# Digital_PWR.net
KiCad netlist of a schematic drawn in Altium Designer
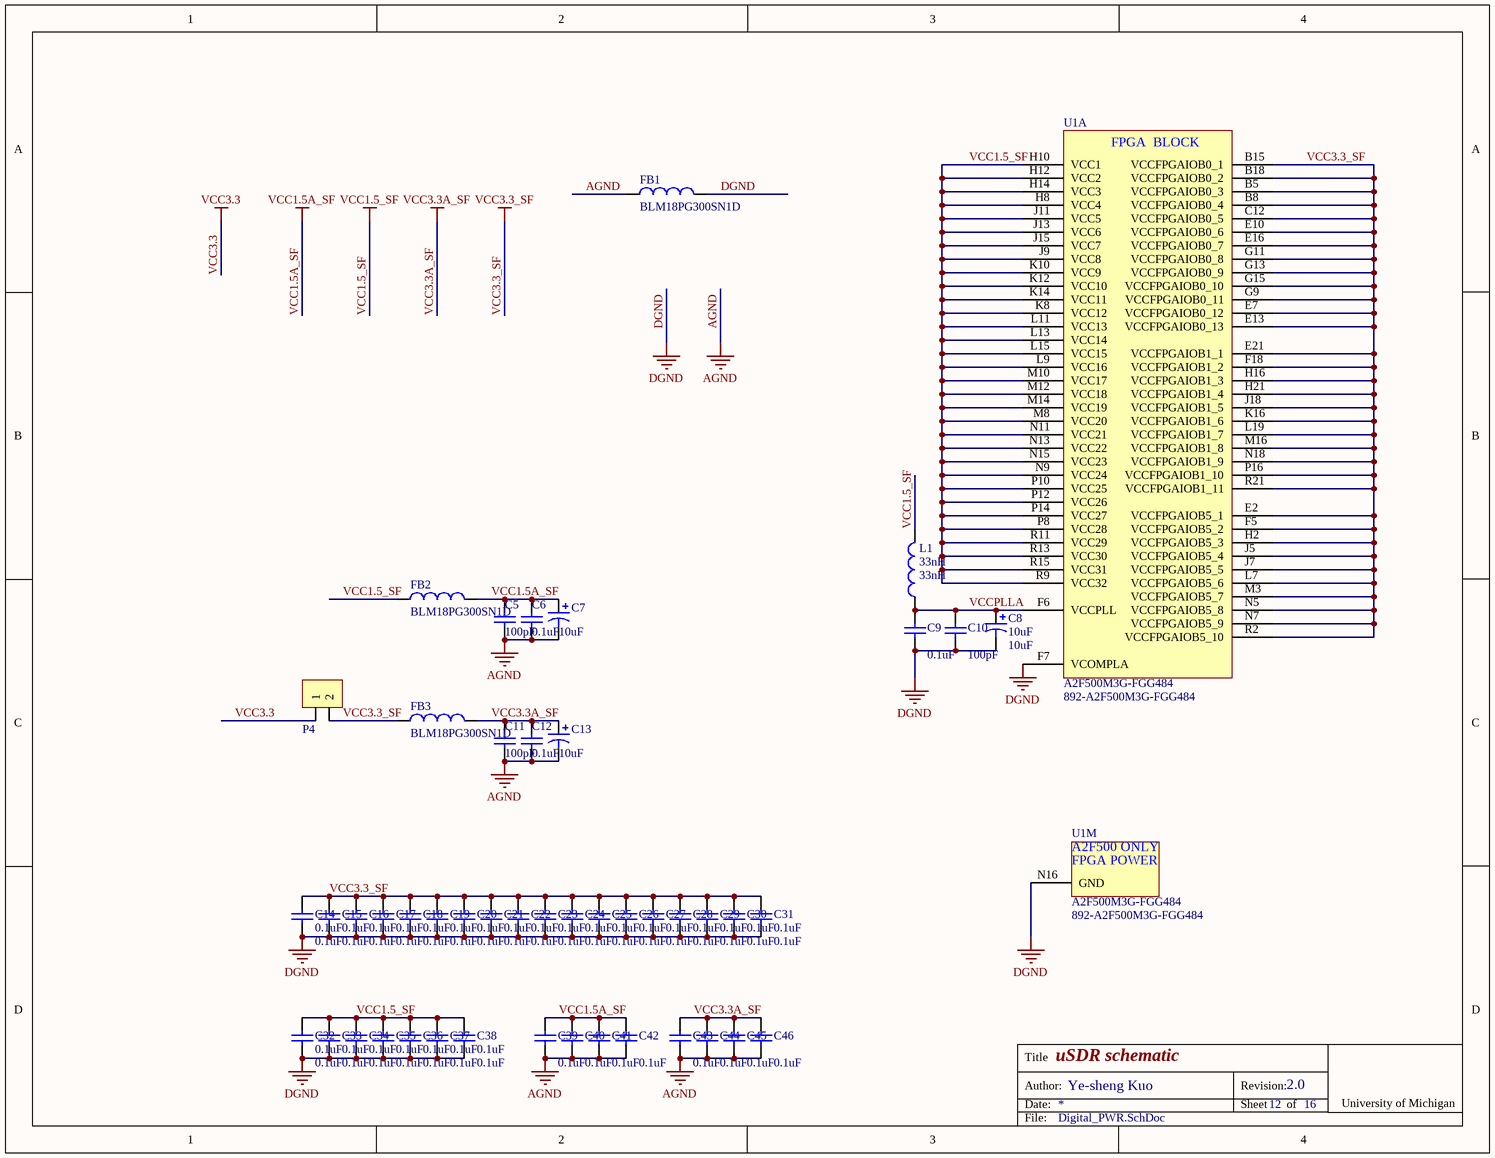
[diagram p0: Digital_PWR.SchDoc]

(export (version "E")
  (design (tool "Eeschema 10.0.6"))
  (components
    (comp (ref "C5")
      (value "100pF")
      (footprint "0402")
      (description "Capacitor (Semiconductor SIM Model)")
      (fields (field (name "PUBLISHER") "Altium Limited"))
      (libsource (lib "Miscellaneous Devices") (part "Cap Semi"))
    )
    (comp (ref "C6")
      (value "0.1uF")
      (footprint "0402")
      (description "Capacitor (Semiconductor SIM Model)")
      (fields (field (name "PUBLISHER") "Altium Limited"))
      (libsource (lib "Miscellaneous Devices") (part "Cap Semi"))
    )
    (comp (ref "C7")
      (value "10uF")
      (footprint "C0805")
      (description "Polarized Capacitor (Surface Mount)")
      (fields (field (name "PUBLISHER") "Altium Limited"))
      (libsource (lib "Miscellaneous Devices") (part "Cap Pol3"))
    )
    (comp (ref "C8")
      (value "10uF")
      (footprint "C0805")
      (description "Polarized Capacitor (Surface Mount)")
      (fields (field (name "ALTIUM_VALUE") "10uF") (field (name "PUBLISHER") "Altium Limited"))
      (libsource (lib "Miscellaneous Devices") (part "Cap Pol3"))
    )
    (comp (ref "C9")
      (value "0.1uF")
      (footprint "0402")
      (description "Capacitor (Semiconductor SIM Model)")
      (fields (field (name "PUBLISHER") "Altium Limited"))
      (libsource (lib "Miscellaneous Devices") (part "Cap Semi"))
    )
    (comp (ref "C10")
      (value "100pF")
      (footprint "0402")
      (description "Capacitor (Semiconductor SIM Model)")
      (fields (field (name "PUBLISHER") "Altium Limited"))
      (libsource (lib "Miscellaneous Devices") (part "Cap Semi"))
    )
    (comp (ref "C11")
      (value "100pF")
      (footprint "0402")
      (description "Capacitor (Semiconductor SIM Model)")
      (fields (field (name "PUBLISHER") "Altium Limited"))
      (libsource (lib "Miscellaneous Devices") (part "Cap Semi"))
    )
    (comp (ref "C12")
      (value "0.1uF")
      (footprint "0402")
      (description "Capacitor (Semiconductor SIM Model)")
      (fields (field (name "PUBLISHER") "Altium Limited"))
      (libsource (lib "Miscellaneous Devices") (part "Cap Semi"))
    )
    (comp (ref "C13")
      (value "10uF")
      (footprint "C0805")
      (description "Polarized Capacitor (Surface Mount)")
      (fields (field (name "PUBLISHER") "Altium Limited"))
      (libsource (lib "Miscellaneous Devices") (part "Cap Pol3"))
    )
    (comp (ref "C14")
      (value "0.1uF")
      (footprint "0402")
      (description "Capacitor (Semiconductor SIM Model)")
      (fields (field (name "ALTIUM_VALUE") "0.1uF") (field (name "PUBLISHER") "Altium Limited"))
      (libsource (lib "Miscellaneous Devices") (part "Cap Semi"))
    )
    (comp (ref "C15")
      (value "0.1uF")
      (footprint "0402")
      (description "Capacitor (Semiconductor SIM Model)")
      (fields (field (name "ALTIUM_VALUE") "0.1uF") (field (name "PUBLISHER") "Altium Limited"))
      (libsource (lib "Miscellaneous Devices") (part "Cap Semi"))
    )
    (comp (ref "C16")
      (value "0.1uF")
      (footprint "0402")
      (description "Capacitor (Semiconductor SIM Model)")
      (fields (field (name "ALTIUM_VALUE") "0.1uF") (field (name "PUBLISHER") "Altium Limited"))
      (libsource (lib "Miscellaneous Devices") (part "Cap Semi"))
    )
    (comp (ref "C17")
      (value "0.1uF")
      (footprint "0402")
      (description "Capacitor (Semiconductor SIM Model)")
      (fields (field (name "ALTIUM_VALUE") "0.1uF") (field (name "PUBLISHER") "Altium Limited"))
      (libsource (lib "Miscellaneous Devices") (part "Cap Semi"))
    )
    (comp (ref "C18")
      (value "0.1uF")
      (footprint "0402")
      (description "Capacitor (Semiconductor SIM Model)")
      (fields (field (name "ALTIUM_VALUE") "0.1uF") (field (name "PUBLISHER") "Altium Limited"))
      (libsource (lib "Miscellaneous Devices") (part "Cap Semi"))
    )
    (comp (ref "C19")
      (value "0.1uF")
      (footprint "0402")
      (description "Capacitor (Semiconductor SIM Model)")
      (fields (field (name "ALTIUM_VALUE") "0.1uF") (field (name "PUBLISHER") "Altium Limited"))
      (libsource (lib "Miscellaneous Devices") (part "Cap Semi"))
    )
    (comp (ref "C20")
      (value "0.1uF")
      (footprint "0402")
      (description "Capacitor (Semiconductor SIM Model)")
      (fields (field (name "ALTIUM_VALUE") "0.1uF") (field (name "PUBLISHER") "Altium Limited"))
      (libsource (lib "Miscellaneous Devices") (part "Cap Semi"))
    )
    (comp (ref "C21")
      (value "0.1uF")
      (footprint "0402")
      (description "Capacitor (Semiconductor SIM Model)")
      (fields (field (name "ALTIUM_VALUE") "0.1uF") (field (name "PUBLISHER") "Altium Limited"))
      (libsource (lib "Miscellaneous Devices") (part "Cap Semi"))
    )
    (comp (ref "C22")
      (value "0.1uF")
      (footprint "0402")
      (description "Capacitor (Semiconductor SIM Model)")
      (fields (field (name "ALTIUM_VALUE") "0.1uF") (field (name "PUBLISHER") "Altium Limited"))
      (libsource (lib "Miscellaneous Devices") (part "Cap Semi"))
    )
    (comp (ref "C23")
      (value "0.1uF")
      (footprint "0402")
      (description "Capacitor (Semiconductor SIM Model)")
      (fields (field (name "ALTIUM_VALUE") "0.1uF") (field (name "PUBLISHER") "Altium Limited"))
      (libsource (lib "Miscellaneous Devices") (part "Cap Semi"))
    )
    (comp (ref "C24")
      (value "0.1uF")
      (footprint "0402")
      (description "Capacitor (Semiconductor SIM Model)")
      (fields (field (name "ALTIUM_VALUE") "0.1uF") (field (name "PUBLISHER") "Altium Limited"))
      (libsource (lib "Miscellaneous Devices") (part "Cap Semi"))
    )
    (comp (ref "C25")
      (value "0.1uF")
      (footprint "0402")
      (description "Capacitor (Semiconductor SIM Model)")
      (fields (field (name "ALTIUM_VALUE") "0.1uF") (field (name "PUBLISHER") "Altium Limited"))
      (libsource (lib "Miscellaneous Devices") (part "Cap Semi"))
    )
    (comp (ref "C26")
      (value "0.1uF")
      (footprint "0402")
      (description "Capacitor (Semiconductor SIM Model)")
      (fields (field (name "ALTIUM_VALUE") "0.1uF") (field (name "PUBLISHER") "Altium Limited"))
      (libsource (lib "Miscellaneous Devices") (part "Cap Semi"))
    )
    (comp (ref "C27")
      (value "0.1uF")
      (footprint "0402")
      (description "Capacitor (Semiconductor SIM Model)")
      (fields (field (name "ALTIUM_VALUE") "0.1uF") (field (name "PUBLISHER") "Altium Limited"))
      (libsource (lib "Miscellaneous Devices") (part "Cap Semi"))
    )
    (comp (ref "C28")
      (value "0.1uF")
      (footprint "0402")
      (description "Capacitor (Semiconductor SIM Model)")
      (fields (field (name "ALTIUM_VALUE") "0.1uF") (field (name "PUBLISHER") "Altium Limited"))
      (libsource (lib "Miscellaneous Devices") (part "Cap Semi"))
    )
    (comp (ref "C29")
      (value "0.1uF")
      (footprint "0402")
      (description "Capacitor (Semiconductor SIM Model)")
      (fields (field (name "ALTIUM_VALUE") "0.1uF") (field (name "PUBLISHER") "Altium Limited"))
      (libsource (lib "Miscellaneous Devices") (part "Cap Semi"))
    )
    (comp (ref "C30")
      (value "0.1uF")
      (footprint "0402")
      (description "Capacitor (Semiconductor SIM Model)")
      (fields (field (name "ALTIUM_VALUE") "0.1uF") (field (name "PUBLISHER") "Altium Limited"))
      (libsource (lib "Miscellaneous Devices") (part "Cap Semi"))
    )
    (comp (ref "C31")
      (value "0.1uF")
      (footprint "0402")
      (description "Capacitor (Semiconductor SIM Model)")
      (fields (field (name "ALTIUM_VALUE") "0.1uF") (field (name "PUBLISHER") "Altium Limited"))
      (libsource (lib "Miscellaneous Devices") (part "Cap Semi"))
    )
    (comp (ref "C32")
      (value "0.1uF")
      (footprint "0402")
      (description "Capacitor (Semiconductor SIM Model)")
      (fields (field (name "ALTIUM_VALUE") "0.1uF") (field (name "PUBLISHER") "Altium Limited"))
      (libsource (lib "Miscellaneous Devices") (part "Cap Semi"))
    )
    (comp (ref "C33")
      (value "0.1uF")
      (footprint "0402")
      (description "Capacitor (Semiconductor SIM Model)")
      (fields (field (name "ALTIUM_VALUE") "0.1uF") (field (name "PUBLISHER") "Altium Limited"))
      (libsource (lib "Miscellaneous Devices") (part "Cap Semi"))
    )
    (comp (ref "C34")
      (value "0.1uF")
      (footprint "0402")
      (description "Capacitor (Semiconductor SIM Model)")
      (fields (field (name "ALTIUM_VALUE") "0.1uF") (field (name "PUBLISHER") "Altium Limited"))
      (libsource (lib "Miscellaneous Devices") (part "Cap Semi"))
    )
    (comp (ref "C35")
      (value "0.1uF")
      (footprint "0402")
      (description "Capacitor (Semiconductor SIM Model)")
      (fields (field (name "ALTIUM_VALUE") "0.1uF") (field (name "PUBLISHER") "Altium Limited"))
      (libsource (lib "Miscellaneous Devices") (part "Cap Semi"))
    )
    (comp (ref "C36")
      (value "0.1uF")
      (footprint "0402")
      (description "Capacitor (Semiconductor SIM Model)")
      (fields (field (name "ALTIUM_VALUE") "0.1uF") (field (name "PUBLISHER") "Altium Limited"))
      (libsource (lib "Miscellaneous Devices") (part "Cap Semi"))
    )
    (comp (ref "C37")
      (value "0.1uF")
      (footprint "0402")
      (description "Capacitor (Semiconductor SIM Model)")
      (fields (field (name "ALTIUM_VALUE") "0.1uF") (field (name "PUBLISHER") "Altium Limited"))
      (libsource (lib "Miscellaneous Devices") (part "Cap Semi"))
    )
    (comp (ref "C38")
      (value "0.1uF")
      (footprint "0402")
      (description "Capacitor (Semiconductor SIM Model)")
      (fields (field (name "ALTIUM_VALUE") "0.1uF") (field (name "PUBLISHER") "Altium Limited"))
      (libsource (lib "Miscellaneous Devices") (part "Cap Semi"))
    )
    (comp (ref "C39")
      (value "0.1uF")
      (footprint "0402")
      (description "Capacitor (Semiconductor SIM Model)")
      (fields (field (name "PUBLISHER") "Altium Limited"))
      (libsource (lib "Miscellaneous Devices") (part "Cap Semi"))
    )
    (comp (ref "C40")
      (value "0.1uF")
      (footprint "0402")
      (description "Capacitor (Semiconductor SIM Model)")
      (fields (field (name "PUBLISHER") "Altium Limited"))
      (libsource (lib "Miscellaneous Devices") (part "Cap Semi"))
    )
    (comp (ref "C41")
      (value "0.1uF")
      (footprint "0402")
      (description "Capacitor (Semiconductor SIM Model)")
      (fields (field (name "PUBLISHER") "Altium Limited"))
      (libsource (lib "Miscellaneous Devices") (part "Cap Semi"))
    )
    (comp (ref "C42")
      (value "0.1uF")
      (footprint "0402")
      (description "Capacitor (Semiconductor SIM Model)")
      (fields (field (name "PUBLISHER") "Altium Limited"))
      (libsource (lib "Miscellaneous Devices") (part "Cap Semi"))
    )
    (comp (ref "C43")
      (value "0.1uF")
      (footprint "0402")
      (description "Capacitor (Semiconductor SIM Model)")
      (fields (field (name "PUBLISHER") "Altium Limited"))
      (libsource (lib "Miscellaneous Devices") (part "Cap Semi"))
    )
    (comp (ref "C44")
      (value "0.1uF")
      (footprint "0402")
      (description "Capacitor (Semiconductor SIM Model)")
      (fields (field (name "PUBLISHER") "Altium Limited"))
      (libsource (lib "Miscellaneous Devices") (part "Cap Semi"))
    )
    (comp (ref "C45")
      (value "0.1uF")
      (footprint "0402")
      (description "Capacitor (Semiconductor SIM Model)")
      (fields (field (name "PUBLISHER") "Altium Limited"))
      (libsource (lib "Miscellaneous Devices") (part "Cap Semi"))
    )
    (comp (ref "C46")
      (value "0.1uF")
      (footprint "0402")
      (description "Capacitor (Semiconductor SIM Model)")
      (fields (field (name "PUBLISHER") "Altium Limited"))
      (libsource (lib "Miscellaneous Devices") (part "Cap Semi"))
    )
    (comp (ref "FB1")
      (value "BLM18PG300SN1D")
      (footprint "1608[0603]")
      (description "FERRITE CHIP 30 OHM 1000MA 0603")
      (libsource (lib "SDR") (part "Ferrite Bead"))
    )
    (comp (ref "FB2")
      (value "BLM18PG300SN1D")
      (footprint "1608[0603]")
      (description "FERRITE CHIP 30 OHM 1000MA 0603")
      (libsource (lib "SDR") (part "Ferrite Bead"))
    )
    (comp (ref "FB3")
      (value "BLM18PG300SN1D")
      (footprint "1608[0603]")
      (description "FERRITE CHIP 30 OHM 1000MA 0603")
      (libsource (lib "SDR") (part "Ferrite Bead"))
    )
    (comp (ref "L1")
      (value "33nH")
      (footprint "0402")
      (description "Inductor")
      (fields (field (name "ALTIUM_VALUE") "33nH") (field (name "PUBLISHER") "Altium Limited"))
      (libsource (lib "Miscellaneous Devices") (part "Inductor"))
    )
    (comp (ref "P4")
      (value "1 x 2 header")
      (footprint "1x2 header")
      (description "100 mils standard header")
      (libsource (lib "SDR") (part "1 x 2 header"))
    )
    (comp (ref "U1")
      (value "A2F500M3G-FGG484")
      (footprint "BGA100P22X22-484N")
      (description "FPGA - Field Programmable Gate Array 500K System Gates")
      (fields (field (name "SUPPLIER PART NUMBER 1") "892-A2F500M3G-FGG484"))
      (libsource (lib "SDR") (part "F2-200_500-FGG484_1"))
    )
  )
  (nets
    (net (code "1") (name "/VCCPLLA") (class "Default")
      (node (ref "C10") (pin "2") (pinfunction "2_2") (pintype "passive"))
      (node (ref "C8") (pin "1") (pinfunction "1_1") (pintype "passive"))
      (node (ref "C9") (pin "2") (pinfunction "2_2") (pintype "passive"))
      (node (ref "L1") (pin "1") (pinfunction "1_1") (pintype "passive"))
      (node (ref "U1") (pin "F6") (pinfunction "VCCPLL_F6") (pintype "power_in"))
    )
    (net (code "2") (name "AGND") (class "Default")
      (node (ref "C11") (pin "1") (pinfunction "1_1") (pintype "passive"))
      (node (ref "C12") (pin "1") (pinfunction "1_1") (pintype "passive"))
      (node (ref "C13") (pin "2") (pinfunction "2_2") (pintype "passive"))
      (node (ref "C39") (pin "1") (pinfunction "1_1") (pintype "passive"))
      (node (ref "C40") (pin "1") (pinfunction "1_1") (pintype "passive"))
      (node (ref "C41") (pin "1") (pinfunction "1_1") (pintype "passive"))
      (node (ref "C42") (pin "1") (pinfunction "1_1") (pintype "passive"))
      (node (ref "C43") (pin "1") (pinfunction "1_1") (pintype "passive"))
      (node (ref "C44") (pin "1") (pinfunction "1_1") (pintype "passive"))
      (node (ref "C45") (pin "1") (pinfunction "1_1") (pintype "passive"))
      (node (ref "C46") (pin "1") (pinfunction "1_1") (pintype "passive"))
      (node (ref "C5") (pin "1") (pinfunction "1_1") (pintype "passive"))
      (node (ref "C6") (pin "1") (pinfunction "1_1") (pintype "passive"))
      (node (ref "C7") (pin "2") (pinfunction "2_2") (pintype "passive"))
      (node (ref "FB1") (pin "1") (pinfunction "1_1") (pintype "passive"))
    )
    (net (code "3") (name "DGND") (class "Default")
      (node (ref "C10") (pin "1") (pinfunction "1_1") (pintype "passive"))
      (node (ref "C14") (pin "1") (pinfunction "1_1") (pintype "passive"))
      (node (ref "C15") (pin "1") (pinfunction "1_1") (pintype "passive"))
      (node (ref "C16") (pin "1") (pinfunction "1_1") (pintype "passive"))
      (node (ref "C17") (pin "1") (pinfunction "1_1") (pintype "passive"))
      (node (ref "C18") (pin "1") (pinfunction "1_1") (pintype "passive"))
      (node (ref "C19") (pin "1") (pinfunction "1_1") (pintype "passive"))
      (node (ref "C20") (pin "1") (pinfunction "1_1") (pintype "passive"))
      (node (ref "C21") (pin "1") (pinfunction "1_1") (pintype "passive"))
      (node (ref "C22") (pin "1") (pinfunction "1_1") (pintype "passive"))
      (node (ref "C23") (pin "1") (pinfunction "1_1") (pintype "passive"))
      (node (ref "C24") (pin "1") (pinfunction "1_1") (pintype "passive"))
      (node (ref "C25") (pin "1") (pinfunction "1_1") (pintype "passive"))
      (node (ref "C26") (pin "1") (pinfunction "1_1") (pintype "passive"))
      (node (ref "C27") (pin "1") (pinfunction "1_1") (pintype "passive"))
      (node (ref "C28") (pin "1") (pinfunction "1_1") (pintype "passive"))
      (node (ref "C29") (pin "1") (pinfunction "1_1") (pintype "passive"))
      (node (ref "C30") (pin "1") (pinfunction "1_1") (pintype "passive"))
      (node (ref "C31") (pin "1") (pinfunction "1_1") (pintype "passive"))
      (node (ref "C32") (pin "1") (pinfunction "1_1") (pintype "passive"))
      (node (ref "C33") (pin "1") (pinfunction "1_1") (pintype "passive"))
      (node (ref "C34") (pin "1") (pinfunction "1_1") (pintype "passive"))
      (node (ref "C35") (pin "1") (pinfunction "1_1") (pintype "passive"))
      (node (ref "C36") (pin "1") (pinfunction "1_1") (pintype "passive"))
      (node (ref "C37") (pin "1") (pinfunction "1_1") (pintype "passive"))
      (node (ref "C38") (pin "1") (pinfunction "1_1") (pintype "passive"))
      (node (ref "C8") (pin "2") (pinfunction "2_2") (pintype "passive"))
      (node (ref "C9") (pin "1") (pinfunction "1_1") (pintype "passive"))
      (node (ref "FB1") (pin "2") (pinfunction "2_2") (pintype "passive"))
      (node (ref "U1") (pin "F7") (pinfunction "VCOMPLA_F7") (pintype "power_in"))
      (node (ref "U1") (pin "N16") (pinfunction "GND_N16") (pintype "power_in"))
    )
    (net (code "4") (name "VCC1.5A_SF") (class "Default")
      (node (ref "C39") (pin "2") (pinfunction "2_2") (pintype "passive"))
      (node (ref "C40") (pin "2") (pinfunction "2_2") (pintype "passive"))
      (node (ref "C41") (pin "2") (pinfunction "2_2") (pintype "passive"))
      (node (ref "C42") (pin "2") (pinfunction "2_2") (pintype "passive"))
      (node (ref "C5") (pin "2") (pinfunction "2_2") (pintype "passive"))
      (node (ref "C6") (pin "2") (pinfunction "2_2") (pintype "passive"))
      (node (ref "C7") (pin "1") (pinfunction "1_1") (pintype "passive"))
      (node (ref "FB2") (pin "2") (pinfunction "2_2") (pintype "passive"))
    )
    (net (code "5") (name "VCC1.5_SF") (class "Default")
      (node (ref "C32") (pin "2") (pinfunction "2_2") (pintype "passive"))
      (node (ref "C33") (pin "2") (pinfunction "2_2") (pintype "passive"))
      (node (ref "C34") (pin "2") (pinfunction "2_2") (pintype "passive"))
      (node (ref "C35") (pin "2") (pinfunction "2_2") (pintype "passive"))
      (node (ref "C36") (pin "2") (pinfunction "2_2") (pintype "passive"))
      (node (ref "C37") (pin "2") (pinfunction "2_2") (pintype "passive"))
      (node (ref "C38") (pin "2") (pinfunction "2_2") (pintype "passive"))
      (node (ref "FB2") (pin "1") (pinfunction "1_1") (pintype "passive"))
      (node (ref "L1") (pin "2") (pinfunction "2_2") (pintype "passive"))
      (node (ref "U1") (pin "H10") (pinfunction "VCC1_H10") (pintype "power_in"))
      (node (ref "U1") (pin "H12") (pinfunction "VCC2_H12") (pintype "power_in"))
      (node (ref "U1") (pin "H14") (pinfunction "VCC3_H14") (pintype "power_in"))
      (node (ref "U1") (pin "H8") (pinfunction "VCC4_H8") (pintype "power_in"))
      (node (ref "U1") (pin "J11") (pinfunction "VCC5_J11") (pintype "power_in"))
      (node (ref "U1") (pin "J13") (pinfunction "VCC6_J13") (pintype "power_in"))
      (node (ref "U1") (pin "J15") (pinfunction "VCC7_J15") (pintype "power_in"))
      (node (ref "U1") (pin "J9") (pinfunction "VCC8_J9") (pintype "power_in"))
      (node (ref "U1") (pin "K10") (pinfunction "VCC9_K10") (pintype "power_in"))
      (node (ref "U1") (pin "K12") (pinfunction "VCC10_K12") (pintype "power_in"))
      (node (ref "U1") (pin "K14") (pinfunction "VCC11_K14") (pintype "power_in"))
      (node (ref "U1") (pin "K8") (pinfunction "VCC12_K8") (pintype "power_in"))
      (node (ref "U1") (pin "L11") (pinfunction "VCC13_L11") (pintype "power_in"))
      (node (ref "U1") (pin "L13") (pinfunction "VCC14_L13") (pintype "power_in"))
      (node (ref "U1") (pin "L15") (pinfunction "VCC15_L15") (pintype "power_in"))
      (node (ref "U1") (pin "L9") (pinfunction "VCC16_L9") (pintype "power_in"))
      (node (ref "U1") (pin "M10") (pinfunction "VCC17_M10") (pintype "power_in"))
      (node (ref "U1") (pin "M12") (pinfunction "VCC18_M12") (pintype "power_in"))
      (node (ref "U1") (pin "M14") (pinfunction "VCC19_M14") (pintype "power_in"))
      (node (ref "U1") (pin "M8") (pinfunction "VCC20_M8") (pintype "power_in"))
      (node (ref "U1") (pin "N11") (pinfunction "VCC21_N11") (pintype "power_in"))
      (node (ref "U1") (pin "N13") (pinfunction "VCC22_N13") (pintype "power_in"))
      (node (ref "U1") (pin "N15") (pinfunction "VCC23_N15") (pintype "power_in"))
      (node (ref "U1") (pin "N9") (pinfunction "VCC24_N9") (pintype "power_in"))
      (node (ref "U1") (pin "P10") (pinfunction "VCC25_P10") (pintype "power_in"))
      (node (ref "U1") (pin "P12") (pinfunction "VCC26_P12") (pintype "power_in"))
      (node (ref "U1") (pin "P14") (pinfunction "VCC27_P14") (pintype "power_in"))
      (node (ref "U1") (pin "P8") (pinfunction "VCC28_P8") (pintype "power_in"))
      (node (ref "U1") (pin "R11") (pinfunction "VCC29_R11") (pintype "power_in"))
      (node (ref "U1") (pin "R13") (pinfunction "VCC30_R13") (pintype "power_in"))
      (node (ref "U1") (pin "R15") (pinfunction "VCC31_R15") (pintype "power_in"))
      (node (ref "U1") (pin "R9") (pinfunction "VCC32_R9") (pintype "power_in"))
    )
    (net (code "6") (name "VCC3.3") (class "Default")
      (node (ref "P4") (pin "1") (pinfunction "1_1") (pintype "passive"))
    )
    (net (code "7") (name "VCC3.3A_SF") (class "Default")
      (node (ref "C11") (pin "2") (pinfunction "2_2") (pintype "passive"))
      (node (ref "C12") (pin "2") (pinfunction "2_2") (pintype "passive"))
      (node (ref "C13") (pin "1") (pinfunction "1_1") (pintype "passive"))
      (node (ref "C43") (pin "2") (pinfunction "2_2") (pintype "passive"))
      (node (ref "C44") (pin "2") (pinfunction "2_2") (pintype "passive"))
      (node (ref "C45") (pin "2") (pinfunction "2_2") (pintype "passive"))
      (node (ref "C46") (pin "2") (pinfunction "2_2") (pintype "passive"))
      (node (ref "FB3") (pin "2") (pinfunction "2_2") (pintype "passive"))
    )
    (net (code "8") (name "VCC3.3_SF") (class "Default")
      (node (ref "C14") (pin "2") (pinfunction "2_2") (pintype "passive"))
      (node (ref "C15") (pin "2") (pinfunction "2_2") (pintype "passive"))
      (node (ref "C16") (pin "2") (pinfunction "2_2") (pintype "passive"))
      (node (ref "C17") (pin "2") (pinfunction "2_2") (pintype "passive"))
      (node (ref "C18") (pin "2") (pinfunction "2_2") (pintype "passive"))
      (node (ref "C19") (pin "2") (pinfunction "2_2") (pintype "passive"))
      (node (ref "C20") (pin "2") (pinfunction "2_2") (pintype "passive"))
      (node (ref "C21") (pin "2") (pinfunction "2_2") (pintype "passive"))
      (node (ref "C22") (pin "2") (pinfunction "2_2") (pintype "passive"))
      (node (ref "C23") (pin "2") (pinfunction "2_2") (pintype "passive"))
      (node (ref "C24") (pin "2") (pinfunction "2_2") (pintype "passive"))
      (node (ref "C25") (pin "2") (pinfunction "2_2") (pintype "passive"))
      (node (ref "C26") (pin "2") (pinfunction "2_2") (pintype "passive"))
      (node (ref "C27") (pin "2") (pinfunction "2_2") (pintype "passive"))
      (node (ref "C28") (pin "2") (pinfunction "2_2") (pintype "passive"))
      (node (ref "C29") (pin "2") (pinfunction "2_2") (pintype "passive"))
      (node (ref "C30") (pin "2") (pinfunction "2_2") (pintype "passive"))
      (node (ref "C31") (pin "2") (pinfunction "2_2") (pintype "passive"))
      (node (ref "FB3") (pin "1") (pinfunction "1_1") (pintype "passive"))
      (node (ref "P4") (pin "2") (pinfunction "2_2") (pintype "passive"))
      (node (ref "U1") (pin "B15") (pinfunction "VCCFPGAIOB0_1_B15") (pintype "power_in"))
      (node (ref "U1") (pin "B18") (pinfunction "VCCFPGAIOB0_2_B18") (pintype "power_in"))
      (node (ref "U1") (pin "B5") (pinfunction "VCCFPGAIOB0_3_B5") (pintype "power_in"))
      (node (ref "U1") (pin "B8") (pinfunction "VCCFPGAIOB0_4_B8") (pintype "power_in"))
      (node (ref "U1") (pin "C12") (pinfunction "VCCFPGAIOB0_5_C12") (pintype "power_in"))
      (node (ref "U1") (pin "E10") (pinfunction "VCCFPGAIOB0_6_E10") (pintype "power_in"))
      (node (ref "U1") (pin "E13") (pinfunction "VCCFPGAIOB0_13_E13") (pintype "power_in"))
      (node (ref "U1") (pin "E16") (pinfunction "VCCFPGAIOB0_7_E16") (pintype "power_in"))
      (node (ref "U1") (pin "E2") (pinfunction "VCCFPGAIOB5_1_E2") (pintype "power_in"))
      (node (ref "U1") (pin "E21") (pinfunction "VCCFPGAIOB1_1_E21") (pintype "power_in"))
      (node (ref "U1") (pin "E7") (pinfunction "VCCFPGAIOB0_12_E7") (pintype "power_in"))
      (node (ref "U1") (pin "F18") (pinfunction "VCCFPGAIOB1_2_F18") (pintype "power_in"))
      (node (ref "U1") (pin "F5") (pinfunction "VCCFPGAIOB5_2_F5") (pintype "power_in"))
      (node (ref "U1") (pin "G11") (pinfunction "VCCFPGAIOB0_8_G11") (pintype "power_in"))
      (node (ref "U1") (pin "G13") (pinfunction "VCCFPGAIOB0_9_G13") (pintype "power_in"))
      (node (ref "U1") (pin "G15") (pinfunction "VCCFPGAIOB0_10_G15") (pintype "power_in"))
      (node (ref "U1") (pin "G9") (pinfunction "VCCFPGAIOB0_11_G9") (pintype "power_in"))
      (node (ref "U1") (pin "H16") (pinfunction "VCCFPGAIOB1_3_H16") (pintype "power_in"))
      (node (ref "U1") (pin "H2") (pinfunction "VCCFPGAIOB5_3_H2") (pintype "power_in"))
      (node (ref "U1") (pin "H21") (pinfunction "VCCFPGAIOB1_4_H21") (pintype "power_in"))
      (node (ref "U1") (pin "J18") (pinfunction "VCCFPGAIOB1_5_J18") (pintype "power_in"))
      (node (ref "U1") (pin "J5") (pinfunction "VCCFPGAIOB5_4_J5") (pintype "power_in"))
      (node (ref "U1") (pin "J7") (pinfunction "VCCFPGAIOB5_5_J7") (pintype "power_in"))
      (node (ref "U1") (pin "K16") (pinfunction "VCCFPGAIOB1_6_K16") (pintype "power_in"))
      (node (ref "U1") (pin "L19") (pinfunction "VCCFPGAIOB1_7_L19") (pintype "power_in"))
      (node (ref "U1") (pin "L7") (pinfunction "VCCFPGAIOB5_6_L7") (pintype "power_in"))
      (node (ref "U1") (pin "M16") (pinfunction "VCCFPGAIOB1_8_M16") (pintype "power_in"))
      (node (ref "U1") (pin "M3") (pinfunction "VCCFPGAIOB5_7_M3") (pintype "power_in"))
      (node (ref "U1") (pin "N18") (pinfunction "VCCFPGAIOB1_9_N18") (pintype "power_in"))
      (node (ref "U1") (pin "N5") (pinfunction "VCCFPGAIOB5_8_N5") (pintype "power_in"))
      (node (ref "U1") (pin "N7") (pinfunction "VCCFPGAIOB5_9_N7") (pintype "power_in"))
      (node (ref "U1") (pin "P16") (pinfunction "VCCFPGAIOB1_10_P16") (pintype "power_in"))
      (node (ref "U1") (pin "R2") (pinfunction "VCCFPGAIOB5_10_R2") (pintype "power_in"))
      (node (ref "U1") (pin "R21") (pinfunction "VCCFPGAIOB1_11_R21") (pintype "power_in"))
    )
  )
)
